# AtmegaRFM69_through_hole.net
KiCad netlist of a schematic drawn in EAGLE
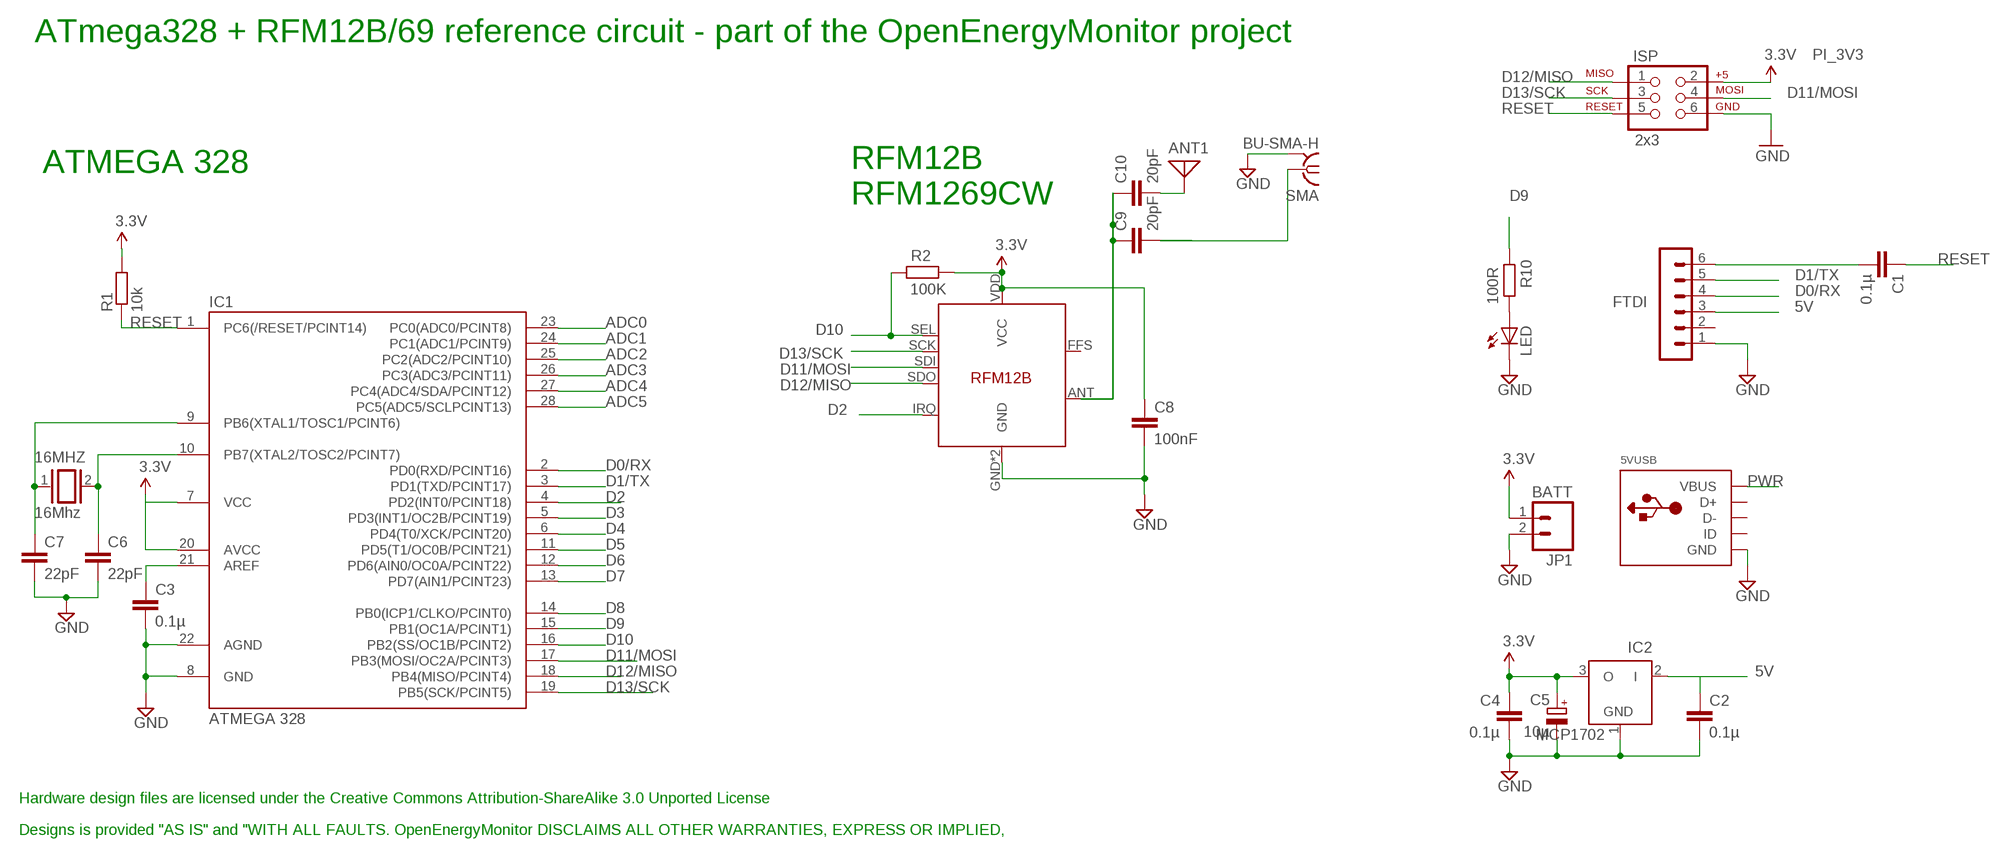
[diagram p0: schematic, sheet 1]

(export (version "E")
  (design (tool "Eeschema 10.0.6"))
  (components
    (comp (ref "5VUSB")
      (value "USBMOLEX")
      (footprint "eagle-import:USB-MINIB-THM-MOLEX")
      (libsource (lib "eagle-import") (part "USBMOLEX"))
    )
    (comp (ref "16MHZ")
      (value "16Mhz")
      (footprint "eagle-import:QS")
      (libsource (lib "eagle-import") (part "XTAL/S"))
    )
    (comp (ref "ANT1")
      (value "ANTENNA")
      (footprint "eagle-import:PAD-01")
      (libsource (lib "eagle-import") (part "ANTENNA"))
    )
    (comp (ref "C1")
      (value "0.1µ")
      (footprint "eagle-import:C025-024X044")
      (libsource (lib "eagle-import") (part "C-EU025-024X044"))
    )
    (comp (ref "C2")
      (value "0.1µ")
      (footprint "eagle-import:C025-024X044")
      (libsource (lib "eagle-import") (part "C-EU025-024X044"))
    )
    (comp (ref "C3")
      (value "0.1µ")
      (footprint "eagle-import:C025-024X044")
      (libsource (lib "eagle-import") (part "C-EU025-024X044"))
    )
    (comp (ref "C4")
      (value "0.1µ")
      (footprint "eagle-import:C025-024X044")
      (libsource (lib "eagle-import") (part "C-EU025-024X044"))
    )
    (comp (ref "C5")
      (value "10µ")
      (footprint "eagle-import:E1,8-4")
      (libsource (lib "eagle-import") (part "CPOL-EUE1.8-4"))
    )
    (comp (ref "C6")
      (value "22pF")
      (footprint "eagle-import:C2.5-2")
      (libsource (lib "eagle-import") (part "C2.5/2"))
    )
    (comp (ref "C7")
      (value "22pF")
      (footprint "eagle-import:C2.5-2")
      (libsource (lib "eagle-import") (part "C2.5/2"))
    )
    (comp (ref "C8")
      (value "100nF")
      (footprint "eagle-import:C025-024X044")
      (libsource (lib "eagle-import") (part "C-EU025-024X044"))
    )
    (comp (ref "C9")
      (value "20pF")
      (footprint "eagle-import:C025-024X044")
      (libsource (lib "eagle-import") (part "C-EU025-024X044"))
    )
    (comp (ref "C10")
      (value "20pF")
      (footprint "eagle-import:C025-024X044")
      (libsource (lib "eagle-import") (part "C-EU025-024X044"))
    )
    (comp (ref "FTDI")
      (value "FTDI")
      (footprint "eagle-import:MA06-1")
      (libsource (lib "eagle-import") (part "MA06-1"))
    )
    (comp (ref "IC1")
      (value "ATMEGA 328")
      (footprint "eagle-import:DIL28-3")
      (libsource (lib "eagle-import") (part "ATMEGA48/88/168-PU"))
    )
    (comp (ref "IC2")
      (value "MCP1702")
      (footprint "eagle-import:TO92")
      (libsource (lib "eagle-import") (part "MCP1702Z"))
    )
    (comp (ref "ISP")
      (value "2x3")
      (footprint "eagle-import:2X3")
      (libsource (lib "eagle-import") (part "AVR_SPI_PRG_6PTH"))
    )
    (comp (ref "JP1")
      (value "BATT")
      (footprint "eagle-import:1X02_LOCK_LONGPADS")
      (libsource (lib "eagle-import") (part "M02LOCK_LONGPADS"))
    )
    (comp (ref "LED")
      (value "LED3MM")
      (footprint "eagle-import:LED3MM")
      (libsource (lib "eagle-import") (part "LED3MM"))
    )
    (comp (ref "R1")
      (value "10k")
      (footprint "eagle-import:0204_7")
      (libsource (lib "eagle-import") (part "resistor_R-EU_0204/7"))
    )
    (comp (ref "R2")
      (value "100K")
      (footprint "eagle-import:0204_7")
      (libsource (lib "eagle-import") (part "R-EU_0204/7"))
    )
    (comp (ref "R10")
      (value "100R")
      (footprint "eagle-import:0204_7")
      (libsource (lib "eagle-import") (part "R-EU_0204/7"))
    )
    (comp (ref "SMA")
      (value "BU-SMA-H")
      (footprint "eagle-import:BU-SMA-H")
      (libsource (lib "eagle-import") (part "BU-SMA-H"))
    )
    (comp (ref "U$14")
      (value "RFM12B")
      (footprint "eagle-import:RFM12B")
      (libsource (lib "eagle-import") (part "RFM12B"))
    )
  )
  (nets
    (net (code "1") (name "/5V") (class "Default")
      (node (ref "C2") (pin "1") (pinfunction "1_1") (pintype "passive"))
      (node (ref "FTDI") (pin "3") (pinfunction "3_3") (pintype "passive"))
      (node (ref "IC2") (pin "2") (pinfunction "I_2") (pintype "input"))
    )
    (net (code "2") (name "/ADC0") (class "Default")
      (node (ref "IC1") (pin "23") (pinfunction "PC0(ADC0/PCINT8)_23") (pintype "bidirectional"))
    )
    (net (code "3") (name "/ADC1") (class "Default")
      (node (ref "IC1") (pin "24") (pinfunction "PC1(ADC1/PCINT9)_24") (pintype "bidirectional"))
    )
    (net (code "4") (name "/ADC2") (class "Default")
      (node (ref "IC1") (pin "25") (pinfunction "PC2(ADC2/PCINT10)_25") (pintype "bidirectional"))
    )
    (net (code "5") (name "/ADC3") (class "Default")
      (node (ref "IC1") (pin "26") (pinfunction "PC3(ADC3/PCINT11)_26") (pintype "bidirectional"))
    )
    (net (code "6") (name "/ADC4") (class "Default")
      (node (ref "IC1") (pin "27") (pinfunction "PC4(ADC4/SDA/PCINT12)_27") (pintype "bidirectional"))
    )
    (net (code "7") (name "/ADC5") (class "Default")
      (node (ref "IC1") (pin "28") (pinfunction "PC5(ADC5/SCLPCINT13)_28") (pintype "bidirectional"))
    )
    (net (code "8") (name "/D0{slash}RX") (class "Default")
      (node (ref "FTDI") (pin "4") (pinfunction "4_4") (pintype "passive"))
      (node (ref "IC1") (pin "2") (pinfunction "PD0(RXD/PCINT16)_2") (pintype "bidirectional"))
    )
    (net (code "9") (name "/D1{slash}TX") (class "Default")
      (node (ref "FTDI") (pin "5") (pinfunction "5_5") (pintype "passive"))
      (node (ref "IC1") (pin "3") (pinfunction "PD1(TXD/PCINT17)_3") (pintype "bidirectional"))
    )
    (net (code "10") (name "/D2") (class "Default")
      (node (ref "IC1") (pin "4") (pinfunction "PD2(INT0/PCINT18)_4") (pintype "bidirectional"))
      (node (ref "U$14") (pin "IRQ") (pinfunction "IRQ_IRQ") (pintype "open_collector"))
    )
    (net (code "11") (name "/D3") (class "Default")
      (node (ref "IC1") (pin "5") (pinfunction "PD3(INT1/OC2B/PCINT19)_5") (pintype "bidirectional"))
    )
    (net (code "12") (name "/D4") (class "Default")
      (node (ref "IC1") (pin "6") (pinfunction "PD4(T0/XCK/PCINT20)_6") (pintype "bidirectional"))
    )
    (net (code "13") (name "/D5") (class "Default")
      (node (ref "IC1") (pin "11") (pinfunction "PD5(T1/OC0B/PCINT21)_11") (pintype "bidirectional"))
    )
    (net (code "14") (name "/D6") (class "Default")
      (node (ref "IC1") (pin "12") (pinfunction "PD6(AIN0/OC0A/PCINT22)_12") (pintype "bidirectional"))
    )
    (net (code "15") (name "/D7") (class "Default")
      (node (ref "IC1") (pin "13") (pinfunction "PD7(AIN1/PCINT23)_13") (pintype "bidirectional"))
    )
    (net (code "16") (name "/D8") (class "Default")
      (node (ref "IC1") (pin "14") (pinfunction "PB0(ICP1/CLKO/PCINT0)_14") (pintype "bidirectional"))
    )
    (net (code "17") (name "/D9") (class "Default")
      (node (ref "IC1") (pin "15") (pinfunction "PB1(OC1A/PCINT1)_15") (pintype "bidirectional"))
      (node (ref "R10") (pin "2") (pinfunction "2_2") (pintype "passive"))
    )
    (net (code "18") (name "/D10") (class "Default")
      (node (ref "IC1") (pin "16") (pinfunction "PB2(SS/OC1B/PCINT2)_16") (pintype "bidirectional"))
      (node (ref "R2") (pin "2") (pinfunction "2_2") (pintype "passive"))
      (node (ref "U$14") (pin "SEL") (pinfunction "SEL_SEL") (pintype "input"))
    )
    (net (code "19") (name "/D11{slash}MOSI") (class "Default")
      (node (ref "IC1") (pin "17") (pinfunction "PB3(MOSI/OC2A/PCINT3)_17") (pintype "bidirectional"))
      (node (ref "ISP") (pin "4") (pinfunction "4_4") (pintype "passive"))
      (node (ref "U$14") (pin "SDI") (pinfunction "SDI_SDI") (pintype "input"))
    )
    (net (code "20") (name "/D12{slash}MISO") (class "Default")
      (node (ref "IC1") (pin "18") (pinfunction "PB4(MISO/PCINT4)_18") (pintype "bidirectional"))
      (node (ref "ISP") (pin "1") (pinfunction "1_1") (pintype "passive"))
      (node (ref "U$14") (pin "SDO") (pinfunction "SDO_SDO") (pintype "output"))
    )
    (net (code "21") (name "/D13{slash}SCK") (class "Default")
      (node (ref "IC1") (pin "19") (pinfunction "PB5(SCK/PCINT5)_19") (pintype "bidirectional"))
      (node (ref "ISP") (pin "3") (pinfunction "3_3") (pintype "passive"))
      (node (ref "U$14") (pin "SCK") (pinfunction "SCK_SCK") (pintype "input"))
    )
    (net (code "23") (name "/PWR") (class "Default")
      (node (ref "5VUSB") (pin "VBUS") (pinfunction "VBUS_VBUS") (pintype "power_in"))
    )
    (net (code "24") (name "/RESET") (class "Default")
      (node (ref "C1") (pin "1") (pinfunction "1_1") (pintype "passive"))
      (node (ref "IC1") (pin "1") (pinfunction "PC6(/RESET/PCINT14)_1") (pintype "bidirectional"))
      (node (ref "ISP") (pin "5") (pinfunction "5_5") (pintype "passive"))
      (node (ref "R1") (pin "1") (pinfunction "1_1") (pintype "passive"))
    )
    (net (code "25") (name "3.3V") (class "Default")
      (node (ref "C4") (pin "1") (pinfunction "1_1") (pintype "passive"))
      (node (ref "C5") (pin "+") (pinfunction "+_+") (pintype "passive"))
      (node (ref "C8") (pin "1") (pinfunction "1_1") (pintype "passive"))
      (node (ref "IC1") (pin "20") (pinfunction "AVCC_20") (pintype "passive"))
      (node (ref "IC1") (pin "7") (pinfunction "VCC_7") (pintype "power_in"))
      (node (ref "IC2") (pin "3") (pinfunction "O_3") (pintype "input"))
      (node (ref "ISP") (pin "2") (pinfunction "2_2") (pintype "passive"))
      (node (ref "JP1") (pin "1") (pinfunction "1_1") (pintype "passive"))
      (node (ref "R1") (pin "2") (pinfunction "2_2") (pintype "passive"))
      (node (ref "R2") (pin "1") (pinfunction "1_1") (pintype "passive"))
      (node (ref "U$14") (pin "VDD") (pinfunction "VCC_VDD") (pintype "power_in"))
    )
    (net (code "26") (name "GND") (class "Default")
      (node (ref "5VUSB") (pin "GND") (pinfunction "GND_GND") (pintype "power_in"))
      (node (ref "C2") (pin "2") (pinfunction "2_2") (pintype "passive"))
      (node (ref "C3") (pin "2") (pinfunction "2_2") (pintype "passive"))
      (node (ref "C4") (pin "2") (pinfunction "2_2") (pintype "passive"))
      (node (ref "C5") (pin "-") (pinfunction "-_-") (pintype "passive"))
      (node (ref "C6") (pin "2") (pinfunction "2_2") (pintype "passive"))
      (node (ref "C7") (pin "2") (pinfunction "2_2") (pintype "passive"))
      (node (ref "C8") (pin "2") (pinfunction "2_2") (pintype "passive"))
      (node (ref "FTDI") (pin "1") (pinfunction "1_1") (pintype "passive"))
      (node (ref "IC1") (pin "22") (pinfunction "AGND_22") (pintype "power_in"))
      (node (ref "IC1") (pin "8") (pinfunction "GND_8") (pintype "power_in"))
      (node (ref "IC2") (pin "1") (pinfunction "GND_1") (pintype "power_in"))
      (node (ref "ISP") (pin "6") (pinfunction "6_6") (pintype "passive"))
      (node (ref "JP1") (pin "2") (pinfunction "2_2") (pintype "passive"))
      (node (ref "LED") (pin "K") (pinfunction "C_K") (pintype "passive"))
      (node (ref "SMA") (pin "2") (pinfunction "2_2") (pintype "passive"))
      (node (ref "SMA") (pin "3") (pinfunction "2_3") (pintype "passive"))
      (node (ref "SMA") (pin "4") (pinfunction "2_4") (pintype "passive"))
      (node (ref "SMA") (pin "5") (pinfunction "2_5") (pintype "passive"))
      (node (ref "U$14") (pin "GND") (pinfunction "GND_GND") (pintype "power_in"))
      (node (ref "U$14") (pin "P$12") (pinfunction "GND_P$12") (pintype "power_in"))
    )
    (net (code "27") (name "Net-(ANT1-Pad1)") (class "Default")
      (node (ref "ANT1") (pin "1") (pinfunction "1_1") (pintype "output"))
      (node (ref "C10") (pin "2") (pinfunction "2_2") (pintype "passive"))
    )
    (net (code "28") (name "Net-(C1-Pad2)") (class "Default")
      (node (ref "C1") (pin "2") (pinfunction "2_2") (pintype "passive"))
      (node (ref "FTDI") (pin "6") (pinfunction "6_6") (pintype "passive"))
    )
    (net (code "29") (name "Net-(C9-Pad2)") (class "Default")
      (node (ref "C9") (pin "2") (pinfunction "2_2") (pintype "passive"))
      (node (ref "SMA") (pin "1") (pinfunction "1_1") (pintype "passive"))
    )
    (net (code "30") (name "Net-(C10-Pad1)") (class "Default")
      (node (ref "C10") (pin "1") (pinfunction "1_1") (pintype "passive"))
      (node (ref "C9") (pin "1") (pinfunction "1_1") (pintype "passive"))
      (node (ref "U$14") (pin "ANT") (pinfunction "ANT_ANT") (pintype "passive"))
    )
    (net (code "31") (name "Net-(IC1-AREF)") (class "Default")
      (node (ref "C3") (pin "1") (pinfunction "1_1") (pintype "passive"))
      (node (ref "IC1") (pin "21") (pinfunction "AREF_21") (pintype "passive"))
    )
    (net (code "32") (name "Net-(IC1-PB6(XTAL1{slash}TOSC1{slash}PCINT6))") (class "Default")
      (node (ref "16MHZ") (pin "1") (pinfunction "1_1") (pintype "passive"))
      (node (ref "C7") (pin "1") (pinfunction "1_1") (pintype "passive"))
      (node (ref "IC1") (pin "9") (pinfunction "PB6(XTAL1/TOSC1/PCINT6)_9") (pintype "bidirectional"))
    )
    (net (code "33") (name "Net-(IC1-PB7(XTAL2{slash}TOSC2{slash}PCINT7))") (class "Default")
      (node (ref "16MHZ") (pin "2") (pinfunction "2_2") (pintype "passive"))
      (node (ref "C6") (pin "1") (pinfunction "1_1") (pintype "passive"))
      (node (ref "IC1") (pin "10") (pinfunction "PB7(XTAL2/TOSC2/PCINT7)_10") (pintype "bidirectional"))
    )
    (net (code "34") (name "Net-(LED-PadA)") (class "Default")
      (node (ref "LED") (pin "A") (pinfunction "A_A") (pintype "passive"))
      (node (ref "R10") (pin "1") (pinfunction "1_1") (pintype "passive"))
    )
    (net (code "35") (name "unconnected-(5VUSB-PadD+)") (class "Default")
      (node (ref "5VUSB") (pin "D+") (pinfunction "D+_D+") (pintype "bidirectional"))
    )
    (net (code "36") (name "unconnected-(5VUSB-PadD-)") (class "Default")
      (node (ref "5VUSB") (pin "D-") (pinfunction "D-_D-") (pintype "bidirectional"))
    )
    (net (code "37") (name "unconnected-(5VUSB-PadID)") (class "Default")
      (node (ref "5VUSB") (pin "ID") (pinfunction "ID_ID") (pintype "bidirectional"))
    )
    (net (code "38") (name "unconnected-(FTDI-Pad2)") (class "Default")
      (node (ref "FTDI") (pin "2") (pinfunction "2_2") (pintype "passive"))
    )
    (net (code "39") (name "unconnected-(U$14-PadFFS)") (class "Default")
      (node (ref "U$14") (pin "FFS") (pinfunction "FFS_FFS") (pintype "bidirectional"))
    )
  )
)
